# Controllable_voltage_outputs.net
KiCad netlist of a schematic drawn in Altium Designer
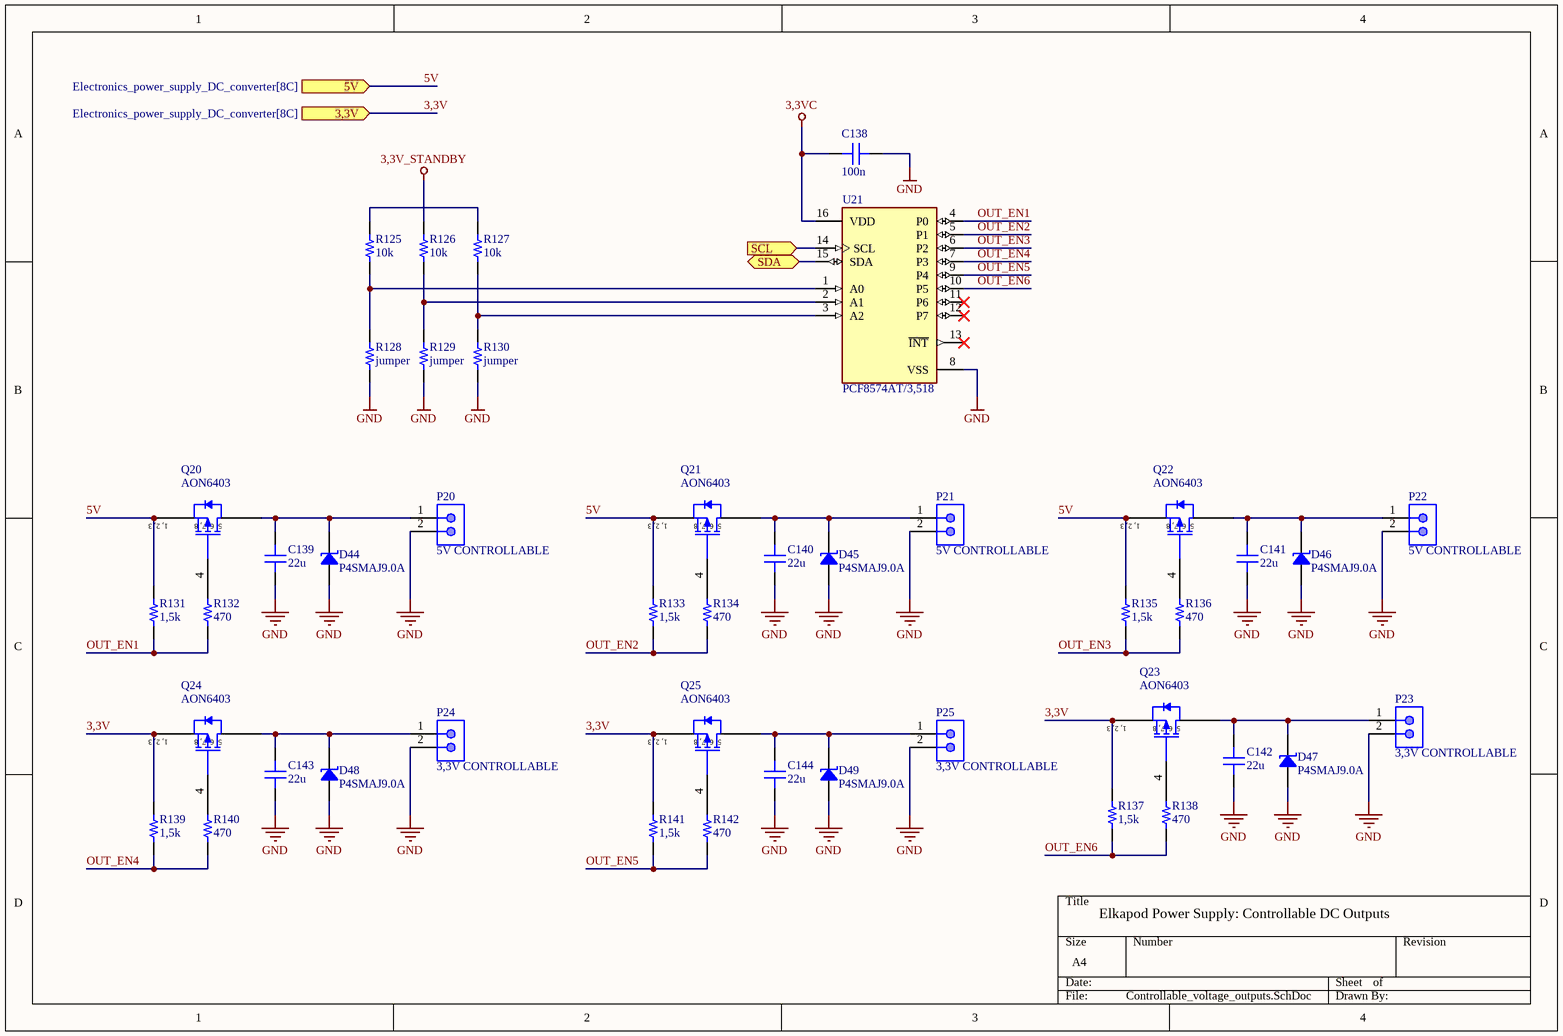
[diagram p0: Controllable_voltage_outputs.SchDoc]

(export (version "E")
  (design (tool "Eeschema 10.0.6"))
  (components
    (comp (ref "C138")
      (value "100n")
      (footprint "CAP 0603_1608")
      (description "CAP CER 100nF 25V X5R 0603")
      (fields (field (name "PART NUMBER") "C0603C272F3GAC7867") (field (name "MANUFACTURER") "KEMET"))
      (libsource (lib "Celestial Altium Library - altium_library") (part "Capacitor"))
    )
    (comp (ref "C139")
      (value "22u")
      (footprint "CAP 0805_2012")
      (description "CAP CER 22UF 25V X7R 0805")
      (fields
        (field (name "PART NUMBER") "VJ0805Y684KXQTW1BC")
        (field (name "MANUFACTURER") "Vishay Vitramon")
      )
      (libsource (lib "Celestial Altium Library - altium_library") (part "Capacitor"))
    )
    (comp (ref "C140")
      (value "22u")
      (footprint "CAP 0805_2012")
      (description "CAP CER 22UF 25V X7R 0805")
      (fields
        (field (name "PART NUMBER") "VJ0805Y684KXQTW1BC")
        (field (name "MANUFACTURER") "Vishay Vitramon")
      )
      (libsource (lib "Celestial Altium Library - altium_library") (part "Capacitor"))
    )
    (comp (ref "C141")
      (value "22u")
      (footprint "CAP 0805_2012")
      (description "CAP CER 22UF 25V X7R 0805")
      (fields
        (field (name "PART NUMBER") "VJ0805Y684KXQTW1BC")
        (field (name "MANUFACTURER") "Vishay Vitramon")
      )
      (libsource (lib "Celestial Altium Library - altium_library") (part "Capacitor"))
    )
    (comp (ref "C142")
      (value "22u")
      (footprint "CAP 0805_2012")
      (description "CAP CER 22UF 25V X7R 0805")
      (fields
        (field (name "PART NUMBER") "VJ0805Y684KXQTW1BC")
        (field (name "MANUFACTURER") "Vishay Vitramon")
      )
      (libsource (lib "Celestial Altium Library - altium_library") (part "Capacitor"))
    )
    (comp (ref "C143")
      (value "22u")
      (footprint "CAP 0805_2012")
      (description "CAP CER 22UF 25V X7R 0805")
      (fields
        (field (name "PART NUMBER") "VJ0805Y684KXQTW1BC")
        (field (name "MANUFACTURER") "Vishay Vitramon")
      )
      (libsource (lib "Celestial Altium Library - altium_library") (part "Capacitor"))
    )
    (comp (ref "C144")
      (value "22u")
      (footprint "CAP 0805_2012")
      (description "CAP CER 22UF 25V X7R 0805")
      (fields
        (field (name "PART NUMBER") "VJ0805Y684KXQTW1BC")
        (field (name "MANUFACTURER") "Vishay Vitramon")
      )
      (libsource (lib "Celestial Altium Library - altium_library") (part "Capacitor"))
    )
    (comp (ref "D44")
      (value "P4SMAJ9.0A")
      (footprint "DO214AC SMA")
      (description "TVS DIODE 9VDC DO214AC")
      (libsource (lib "Celestial Altium Library - altium_library") (part "DIODE TVS UNI"))
    )
    (comp (ref "D45")
      (value "P4SMAJ9.0A")
      (footprint "DO214AC SMA")
      (description "TVS DIODE 9VDC DO214AC")
      (libsource (lib "Celestial Altium Library - altium_library") (part "DIODE TVS UNI"))
    )
    (comp (ref "D46")
      (value "P4SMAJ9.0A")
      (footprint "DO214AC SMA")
      (description "TVS DIODE 9VDC DO214AC")
      (libsource (lib "Celestial Altium Library - altium_library") (part "DIODE TVS UNI"))
    )
    (comp (ref "D47")
      (value "P4SMAJ9.0A")
      (footprint "DO214AC SMA")
      (description "TVS DIODE 9VDC DO214AC")
      (libsource (lib "Celestial Altium Library - altium_library") (part "DIODE TVS UNI"))
    )
    (comp (ref "D48")
      (value "P4SMAJ9.0A")
      (footprint "DO214AC SMA")
      (description "TVS DIODE 9VDC DO214AC")
      (libsource (lib "Celestial Altium Library - altium_library") (part "DIODE TVS UNI"))
    )
    (comp (ref "D49")
      (value "P4SMAJ9.0A")
      (footprint "DO214AC SMA")
      (description "TVS DIODE 9VDC DO214AC")
      (libsource (lib "Celestial Altium Library - altium_library") (part "DIODE TVS UNI"))
    )
    (comp (ref "P20")
      (value "5V CONTROLLABLE")
      (footprint "MOLX-22-23-2021_V")
      (fields (field (name "PARTNUMBER") "22-23-2021"))
      (libsource (lib "Altium Content Vault") (part "CN-1P-M-R2"))
    )
    (comp (ref "P21")
      (value "5V CONTROLLABLE")
      (footprint "MOLX-22-23-2021_V")
      (fields (field (name "PARTNUMBER") "22-23-2021"))
      (libsource (lib "Altium Content Vault") (part "CN-1P-M-R2"))
    )
    (comp (ref "P22")
      (value "5V CONTROLLABLE")
      (footprint "MOLX-22-23-2021_V")
      (fields (field (name "PARTNUMBER") "22-23-2021"))
      (libsource (lib "Altium Content Vault") (part "CN-1P-M-R2"))
    )
    (comp (ref "P23")
      (value "3,3V CONTROLLABLE")
      (footprint "MOLX-22-23-2021_V")
      (fields (field (name "PARTNUMBER") "22-23-2021"))
      (libsource (lib "Altium Content Vault") (part "CN-1P-M-R2"))
    )
    (comp (ref "P24")
      (value "3,3V CONTROLLABLE")
      (footprint "MOLX-22-23-2021_V")
      (fields (field (name "PARTNUMBER") "22-23-2021"))
      (libsource (lib "Altium Content Vault") (part "CN-1P-M-R2"))
    )
    (comp (ref "P25")
      (value "3,3V CONTROLLABLE")
      (footprint "MOLX-22-23-2021_V")
      (fields (field (name "PARTNUMBER") "22-23-2021"))
      (libsource (lib "Altium Content Vault") (part "CN-1P-M-R2"))
    )
    (comp (ref "Q20")
      (value "AON6403")
      (footprint "DFN5x6")
      (description "P-MOSFET; 67A; 30V; DFN5x6")
      (libsource (lib "My_transistors") (part "AON6403"))
    )
    (comp (ref "Q21")
      (value "AON6403")
      (footprint "DFN5x6")
      (description "P-MOSFET; 67A; 30V; DFN5x6")
      (libsource (lib "My_transistors") (part "AON6403"))
    )
    (comp (ref "Q22")
      (value "AON6403")
      (footprint "DFN5x6")
      (description "P-MOSFET; 67A; 30V; DFN5x6")
      (libsource (lib "My_transistors") (part "AON6403"))
    )
    (comp (ref "Q23")
      (value "AON6403")
      (footprint "DFN5x6")
      (description "P-MOSFET; 67A; 30V; DFN5x6")
      (libsource (lib "My_transistors") (part "AON6403"))
    )
    (comp (ref "Q24")
      (value "AON6403")
      (footprint "DFN5x6")
      (description "P-MOSFET; 67A; 30V; DFN5x6")
      (libsource (lib "My_transistors") (part "AON6403"))
    )
    (comp (ref "Q25")
      (value "AON6403")
      (footprint "DFN5x6")
      (description "P-MOSFET; 67A; 30V; DFN5x6")
      (libsource (lib "My_transistors") (part "AON6403"))
    )
    (comp (ref "R125")
      (value "10k")
      (footprint "RES 0603_1608")
      (description "RES 10K OHM 1% 0,1W 0603")
      (fields
        (field (name "PART NUMBER") "RNCS0603BKE10K0")
        (field (name "MANUFACTURER") "Stackpole Electronics Inc")
      )
      (libsource (lib "Celestial Altium Library - altium_library") (part "Resistor"))
    )
    (comp (ref "R126")
      (value "10k")
      (footprint "RES 0603_1608")
      (description "RES 10K OHM 1% 0,1W 0603")
      (fields
        (field (name "PART NUMBER") "RNCS0603BKE10K0")
        (field (name "MANUFACTURER") "Stackpole Electronics Inc")
      )
      (libsource (lib "Celestial Altium Library - altium_library") (part "Resistor"))
    )
    (comp (ref "R127")
      (value "10k")
      (footprint "RES 0603_1608")
      (description "RES 10K OHM 1% 0,1W 0603")
      (fields
        (field (name "PART NUMBER") "RNCS0603BKE10K0")
        (field (name "MANUFACTURER") "Stackpole Electronics Inc")
      )
      (libsource (lib "Celestial Altium Library - altium_library") (part "Resistor"))
    )
    (comp (ref "R128")
      (value "jumper")
      (footprint "RES 0603_1608")
      (description "RES 0 OHM 1% 0,1W 0603")
      (fields
        (field (name "PART NUMBER") "RNCS0603BKE10K0")
        (field (name "MANUFACTURER") "Stackpole Electronics Inc")
      )
      (libsource (lib "Celestial Altium Library - altium_library") (part "Resistor"))
    )
    (comp (ref "R129")
      (value "jumper")
      (footprint "RES 0603_1608")
      (description "RES 0 OHM 1% 0,1W 0603")
      (fields
        (field (name "PART NUMBER") "RNCS0603BKE10K0")
        (field (name "MANUFACTURER") "Stackpole Electronics Inc")
      )
      (libsource (lib "Celestial Altium Library - altium_library") (part "Resistor"))
    )
    (comp (ref "R130")
      (value "jumper")
      (footprint "RES 0603_1608")
      (description "RES 0 OHM 1% 0,1W 0603")
      (fields
        (field (name "PART NUMBER") "RNCS0603BKE10K0")
        (field (name "MANUFACTURER") "Stackpole Electronics Inc")
      )
      (libsource (lib "Celestial Altium Library - altium_library") (part "Resistor"))
    )
    (comp (ref "R131")
      (value "1,5k")
      (footprint "RES 0603_1608")
      (description "RES 1,5K OHM 1% 0,1W 0603")
      (fields
        (field (name "PART NUMBER") "RNCS0603BKE10K0")
        (field (name "MANUFACTURER") "Stackpole Electronics Inc")
      )
      (libsource (lib "Celestial Altium Library - altium_library") (part "Resistor"))
    )
    (comp (ref "R132")
      (value "470")
      (footprint "RES 0603_1608")
      (description "RES 470 OHM 1% 0,1W 0603")
      (fields
        (field (name "PART NUMBER") "RNCS0603BKE10K0")
        (field (name "MANUFACTURER") "Stackpole Electronics Inc")
      )
      (libsource (lib "Celestial Altium Library - altium_library") (part "Resistor"))
    )
    (comp (ref "R133")
      (value "1,5k")
      (footprint "RES 0603_1608")
      (description "RES 1,5K OHM 1% 0,1W 0603")
      (fields
        (field (name "PART NUMBER") "RNCS0603BKE10K0")
        (field (name "MANUFACTURER") "Stackpole Electronics Inc")
      )
      (libsource (lib "Celestial Altium Library - altium_library") (part "Resistor"))
    )
    (comp (ref "R134")
      (value "470")
      (footprint "RES 0603_1608")
      (description "RES 470 OHM 1% 0,1W 0603")
      (fields
        (field (name "PART NUMBER") "RNCS0603BKE10K0")
        (field (name "MANUFACTURER") "Stackpole Electronics Inc")
      )
      (libsource (lib "Celestial Altium Library - altium_library") (part "Resistor"))
    )
    (comp (ref "R135")
      (value "1,5k")
      (footprint "RES 0603_1608")
      (description "RES 1,5K OHM 1% 0,1W 0603")
      (fields
        (field (name "PART NUMBER") "RNCS0603BKE10K0")
        (field (name "MANUFACTURER") "Stackpole Electronics Inc")
      )
      (libsource (lib "Celestial Altium Library - altium_library") (part "Resistor"))
    )
    (comp (ref "R136")
      (value "470")
      (footprint "RES 0603_1608")
      (description "RES 470 OHM 1% 0,1W 0603")
      (fields
        (field (name "PART NUMBER") "RNCS0603BKE10K0")
        (field (name "MANUFACTURER") "Stackpole Electronics Inc")
      )
      (libsource (lib "Celestial Altium Library - altium_library") (part "Resistor"))
    )
    (comp (ref "R137")
      (value "1,5k")
      (footprint "RES 0603_1608")
      (description "RES 1,5K OHM 1% 0,1W 0603")
      (fields
        (field (name "PART NUMBER") "RNCS0603BKE10K0")
        (field (name "MANUFACTURER") "Stackpole Electronics Inc")
      )
      (libsource (lib "Celestial Altium Library - altium_library") (part "Resistor"))
    )
    (comp (ref "R138")
      (value "470")
      (footprint "RES 0603_1608")
      (description "RES 470 OHM 1% 0,1W 0603")
      (fields
        (field (name "PART NUMBER") "RNCS0603BKE10K0")
        (field (name "MANUFACTURER") "Stackpole Electronics Inc")
      )
      (libsource (lib "Celestial Altium Library - altium_library") (part "Resistor"))
    )
    (comp (ref "R139")
      (value "1,5k")
      (footprint "RES 0603_1608")
      (description "RES 1,5K OHM 1% 0,1W 0603")
      (fields
        (field (name "PART NUMBER") "RNCS0603BKE10K0")
        (field (name "MANUFACTURER") "Stackpole Electronics Inc")
      )
      (libsource (lib "Celestial Altium Library - altium_library") (part "Resistor"))
    )
    (comp (ref "R140")
      (value "470")
      (footprint "RES 0603_1608")
      (description "RES 470 OHM 1% 0,1W 0603")
      (fields
        (field (name "PART NUMBER") "RNCS0603BKE10K0")
        (field (name "MANUFACTURER") "Stackpole Electronics Inc")
      )
      (libsource (lib "Celestial Altium Library - altium_library") (part "Resistor"))
    )
    (comp (ref "R141")
      (value "1,5k")
      (footprint "RES 0603_1608")
      (description "RES 1,5K OHM 1% 0,1W 0603")
      (fields
        (field (name "PART NUMBER") "RNCS0603BKE10K0")
        (field (name "MANUFACTURER") "Stackpole Electronics Inc")
      )
      (libsource (lib "Celestial Altium Library - altium_library") (part "Resistor"))
    )
    (comp (ref "R142")
      (value "470")
      (footprint "RES 0603_1608")
      (description "RES 470 OHM 1% 0,1W 0603")
      (fields
        (field (name "PART NUMBER") "RNCS0603BKE10K0")
        (field (name "MANUFACTURER") "Stackpole Electronics Inc")
      )
      (libsource (lib "Celestial Altium Library - altium_library") (part "Resistor"))
    )
    (comp (ref "U21")
      (value "PCF8574AT/3,518")
      (footprint "FP-SOT162-1-MFG")
      (description "IC I/O EXPANDER I2C 8B 16SOIC")
      (fields
        (field (name "MANUFACTURER") "NXP Semiconductors")
        (field (name "OCTOPART") "https://octopart.com/pcf8574at%2F3%2C518-nxp+semiconductors-11541925")
      )
      (libsource (lib "Altium Content Vault") (part "f7fde53ce59de981fb0b266a4e103eb"))
    )
  )
  (nets
    (net (code "1") (name "/3,3V") (class "Default")
      (node (ref "Q23") (pin "1") (pinfunction "S_1") (pintype "passive"))
      (node (ref "Q23") (pin "2") (pinfunction "S_2") (pintype "passive"))
      (node (ref "Q23") (pin "3") (pinfunction "S_3") (pintype "passive"))
      (node (ref "Q24") (pin "1") (pinfunction "S_1") (pintype "passive"))
      (node (ref "Q24") (pin "2") (pinfunction "S_2") (pintype "passive"))
      (node (ref "Q24") (pin "3") (pinfunction "S_3") (pintype "passive"))
      (node (ref "Q25") (pin "1") (pinfunction "S_1") (pintype "passive"))
      (node (ref "Q25") (pin "2") (pinfunction "S_2") (pintype "passive"))
      (node (ref "Q25") (pin "3") (pinfunction "S_3") (pintype "passive"))
      (node (ref "R137") (pin "1") (pinfunction "1_1") (pintype "passive"))
      (node (ref "R139") (pin "1") (pinfunction "1_1") (pintype "passive"))
      (node (ref "R141") (pin "1") (pinfunction "1_1") (pintype "passive"))
    )
    (net (code "2") (name "/5V") (class "Default")
      (node (ref "Q20") (pin "1") (pinfunction "S_1") (pintype "passive"))
      (node (ref "Q20") (pin "2") (pinfunction "S_2") (pintype "passive"))
      (node (ref "Q20") (pin "3") (pinfunction "S_3") (pintype "passive"))
      (node (ref "Q21") (pin "1") (pinfunction "S_1") (pintype "passive"))
      (node (ref "Q21") (pin "2") (pinfunction "S_2") (pintype "passive"))
      (node (ref "Q21") (pin "3") (pinfunction "S_3") (pintype "passive"))
      (node (ref "Q22") (pin "1") (pinfunction "S_1") (pintype "passive"))
      (node (ref "Q22") (pin "2") (pinfunction "S_2") (pintype "passive"))
      (node (ref "Q22") (pin "3") (pinfunction "S_3") (pintype "passive"))
      (node (ref "R131") (pin "1") (pinfunction "1_1") (pintype "passive"))
      (node (ref "R133") (pin "1") (pinfunction "1_1") (pintype "passive"))
      (node (ref "R135") (pin "1") (pinfunction "1_1") (pintype "passive"))
    )
    (net (code "3") (name "/OUT_EN1") (class "Default")
      (node (ref "R131") (pin "2") (pinfunction "2_2") (pintype "passive"))
      (node (ref "R132") (pin "2") (pinfunction "2_2") (pintype "passive"))
      (node (ref "U21") (pin "4") (pinfunction "P0_4") (pintype "bidirectional"))
    )
    (net (code "4") (name "/OUT_EN2") (class "Default")
      (node (ref "R133") (pin "2") (pinfunction "2_2") (pintype "passive"))
      (node (ref "R134") (pin "2") (pinfunction "2_2") (pintype "passive"))
      (node (ref "U21") (pin "5") (pinfunction "P1_5") (pintype "bidirectional"))
    )
    (net (code "5") (name "/OUT_EN3") (class "Default")
      (node (ref "R135") (pin "2") (pinfunction "2_2") (pintype "passive"))
      (node (ref "R136") (pin "2") (pinfunction "2_2") (pintype "passive"))
      (node (ref "U21") (pin "6") (pinfunction "P2_6") (pintype "bidirectional"))
    )
    (net (code "6") (name "/OUT_EN4") (class "Default")
      (node (ref "R139") (pin "2") (pinfunction "2_2") (pintype "passive"))
      (node (ref "R140") (pin "2") (pinfunction "2_2") (pintype "passive"))
      (node (ref "U21") (pin "7") (pinfunction "P3_7") (pintype "bidirectional"))
    )
    (net (code "7") (name "/OUT_EN5") (class "Default")
      (node (ref "R141") (pin "2") (pinfunction "2_2") (pintype "passive"))
      (node (ref "R142") (pin "2") (pinfunction "2_2") (pintype "passive"))
      (node (ref "U21") (pin "9") (pinfunction "P4_9") (pintype "bidirectional"))
    )
    (net (code "8") (name "/OUT_EN6") (class "Default")
      (node (ref "R137") (pin "2") (pinfunction "2_2") (pintype "passive"))
      (node (ref "R138") (pin "2") (pinfunction "2_2") (pintype "passive"))
      (node (ref "U21") (pin "10") (pinfunction "P5_10") (pintype "bidirectional"))
    )
    (net (code "9") (name "/SCL") (class "Default")
      (node (ref "U21") (pin "14") (pinfunction "SCL_14") (pintype "input"))
    )
    (net (code "10") (name "/SDA") (class "Default")
      (node (ref "U21") (pin "15") (pinfunction "SDA_15") (pintype "bidirectional"))
    )
    (net (code "11") (name "3,3VC") (class "Default")
      (node (ref "C138") (pin "2") (pinfunction "2_2") (pintype "passive"))
      (node (ref "U21") (pin "16") (pinfunction "VDD_16") (pintype "power_in"))
    )
    (net (code "12") (name "3,3V_STANDBY") (class "Default")
      (node (ref "R126") (pin "1") (pinfunction "1_1") (pintype "passive"))
    )
    (net (code "13") (name "GND") (class "Default")
      (node (ref "C138") (pin "1") (pinfunction "1_1") (pintype "passive"))
      (node (ref "C139") (pin "1") (pinfunction "1_1") (pintype "passive"))
      (node (ref "C140") (pin "1") (pinfunction "1_1") (pintype "passive"))
      (node (ref "C141") (pin "1") (pinfunction "1_1") (pintype "passive"))
      (node (ref "C142") (pin "1") (pinfunction "1_1") (pintype "passive"))
      (node (ref "C143") (pin "1") (pinfunction "1_1") (pintype "passive"))
      (node (ref "C144") (pin "1") (pinfunction "1_1") (pintype "passive"))
      (node (ref "D44") (pin "1") (pinfunction "1_1") (pintype "passive"))
      (node (ref "D45") (pin "1") (pinfunction "1_1") (pintype "passive"))
      (node (ref "D46") (pin "1") (pinfunction "1_1") (pintype "passive"))
      (node (ref "D47") (pin "1") (pinfunction "1_1") (pintype "passive"))
      (node (ref "D48") (pin "1") (pinfunction "1_1") (pintype "passive"))
      (node (ref "D49") (pin "1") (pinfunction "1_1") (pintype "passive"))
      (node (ref "P20") (pin "2") (pinfunction "2_2") (pintype "passive"))
      (node (ref "P21") (pin "2") (pinfunction "2_2") (pintype "passive"))
      (node (ref "P22") (pin "2") (pinfunction "2_2") (pintype "passive"))
      (node (ref "P23") (pin "2") (pinfunction "2_2") (pintype "passive"))
      (node (ref "P24") (pin "2") (pinfunction "2_2") (pintype "passive"))
      (node (ref "P25") (pin "2") (pinfunction "2_2") (pintype "passive"))
      (node (ref "R128") (pin "2") (pinfunction "2_2") (pintype "passive"))
      (node (ref "R129") (pin "2") (pinfunction "2_2") (pintype "passive"))
      (node (ref "R130") (pin "2") (pinfunction "2_2") (pintype "passive"))
      (node (ref "U21") (pin "8") (pinfunction "VSS_8") (pintype "power_in"))
    )
    (net (code "14") (name "Net-(Q20-D)") (class "Default")
      (node (ref "C139") (pin "2") (pinfunction "2_2") (pintype "passive"))
      (node (ref "D44") (pin "2") (pinfunction "2_2") (pintype "passive"))
      (node (ref "P20") (pin "1") (pinfunction "1_1") (pintype "passive"))
      (node (ref "Q20") (pin "5-6-7-8") (pinfunction "D_5-6-7-8") (pintype "passive"))
    )
    (net (code "15") (name "Net-(Q20-G)") (class "Default")
      (node (ref "Q20") (pin "4") (pinfunction "G_4") (pintype "passive"))
      (node (ref "R132") (pin "1") (pinfunction "1_1") (pintype "passive"))
    )
    (net (code "16") (name "Net-(Q21-D)") (class "Default")
      (node (ref "C140") (pin "2") (pinfunction "2_2") (pintype "passive"))
      (node (ref "D45") (pin "2") (pinfunction "2_2") (pintype "passive"))
      (node (ref "P21") (pin "1") (pinfunction "1_1") (pintype "passive"))
      (node (ref "Q21") (pin "5-6-7-8") (pinfunction "D_5-6-7-8") (pintype "passive"))
    )
    (net (code "17") (name "Net-(Q21-G)") (class "Default")
      (node (ref "Q21") (pin "4") (pinfunction "G_4") (pintype "passive"))
      (node (ref "R134") (pin "1") (pinfunction "1_1") (pintype "passive"))
    )
    (net (code "18") (name "Net-(Q22-D)") (class "Default")
      (node (ref "C141") (pin "2") (pinfunction "2_2") (pintype "passive"))
      (node (ref "D46") (pin "2") (pinfunction "2_2") (pintype "passive"))
      (node (ref "P22") (pin "1") (pinfunction "1_1") (pintype "passive"))
      (node (ref "Q22") (pin "5-6-7-8") (pinfunction "D_5-6-7-8") (pintype "passive"))
    )
    (net (code "19") (name "Net-(Q22-G)") (class "Default")
      (node (ref "Q22") (pin "4") (pinfunction "G_4") (pintype "passive"))
      (node (ref "R136") (pin "1") (pinfunction "1_1") (pintype "passive"))
    )
    (net (code "20") (name "Net-(Q23-D)") (class "Default")
      (node (ref "C142") (pin "2") (pinfunction "2_2") (pintype "passive"))
      (node (ref "D47") (pin "2") (pinfunction "2_2") (pintype "passive"))
      (node (ref "P23") (pin "1") (pinfunction "1_1") (pintype "passive"))
      (node (ref "Q23") (pin "5-6-7-8") (pinfunction "D_5-6-7-8") (pintype "passive"))
    )
    (net (code "21") (name "Net-(Q23-G)") (class "Default")
      (node (ref "Q23") (pin "4") (pinfunction "G_4") (pintype "passive"))
      (node (ref "R138") (pin "1") (pinfunction "1_1") (pintype "passive"))
    )
    (net (code "22") (name "Net-(Q24-D)") (class "Default")
      (node (ref "C143") (pin "2") (pinfunction "2_2") (pintype "passive"))
      (node (ref "D48") (pin "2") (pinfunction "2_2") (pintype "passive"))
      (node (ref "P24") (pin "1") (pinfunction "1_1") (pintype "passive"))
      (node (ref "Q24") (pin "5-6-7-8") (pinfunction "D_5-6-7-8") (pintype "passive"))
    )
    (net (code "23") (name "Net-(Q24-G)") (class "Default")
      (node (ref "Q24") (pin "4") (pinfunction "G_4") (pintype "passive"))
      (node (ref "R140") (pin "1") (pinfunction "1_1") (pintype "passive"))
    )
    (net (code "24") (name "Net-(Q25-D)") (class "Default")
      (node (ref "C144") (pin "2") (pinfunction "2_2") (pintype "passive"))
      (node (ref "D49") (pin "2") (pinfunction "2_2") (pintype "passive"))
      (node (ref "P25") (pin "1") (pinfunction "1_1") (pintype "passive"))
      (node (ref "Q25") (pin "5-6-7-8") (pinfunction "D_5-6-7-8") (pintype "passive"))
    )
    (net (code "25") (name "Net-(Q25-G)") (class "Default")
      (node (ref "Q25") (pin "4") (pinfunction "G_4") (pintype "passive"))
      (node (ref "R142") (pin "1") (pinfunction "1_1") (pintype "passive"))
    )
    (net (code "26") (name "Net-(R125-Pad1)") (class "Default")
      (node (ref "R125") (pin "1") (pinfunction "1_1") (pintype "passive"))
      (node (ref "R127") (pin "1") (pinfunction "1_1") (pintype "passive"))
    )
    (net (code "27") (name "Net-(U21-A0)") (class "Default")
      (node (ref "R125") (pin "2") (pinfunction "2_2") (pintype "passive"))
      (node (ref "R128") (pin "1") (pinfunction "1_1") (pintype "passive"))
      (node (ref "U21") (pin "1") (pinfunction "A0_1") (pintype "input"))
    )
    (net (code "28") (name "Net-(U21-A1)") (class "Default")
      (node (ref "R126") (pin "2") (pinfunction "2_2") (pintype "passive"))
      (node (ref "R129") (pin "1") (pinfunction "1_1") (pintype "passive"))
      (node (ref "U21") (pin "2") (pinfunction "A1_2") (pintype "input"))
    )
    (net (code "29") (name "Net-(U21-A2)") (class "Default")
      (node (ref "R127") (pin "2") (pinfunction "2_2") (pintype "passive"))
      (node (ref "R130") (pin "1") (pinfunction "1_1") (pintype "passive"))
      (node (ref "U21") (pin "3") (pinfunction "A2_3") (pintype "input"))
    )
    (net (code "30") (name "unconnected-(U21-P6-Pad11)") (class "Default")
      (node (ref "U21") (pin "11") (pinfunction "P6_11") (pintype "bidirectional+no_connect"))
    )
    (net (code "31") (name "unconnected-(U21-P7-Pad12)") (class "Default")
      (node (ref "U21") (pin "12") (pinfunction "P7_12") (pintype "bidirectional+no_connect"))
    )
    (net (code "32") (name "unconnected-(U21-~{INT}-Pad13)") (class "Default")
      (node (ref "U21") (pin "13") (pinfunction "~{INT}_13") (pintype "output+no_connect"))
    )
  )
)
